# ICDI.net
KiCad netlist of a schematic drawn in Altium Designer
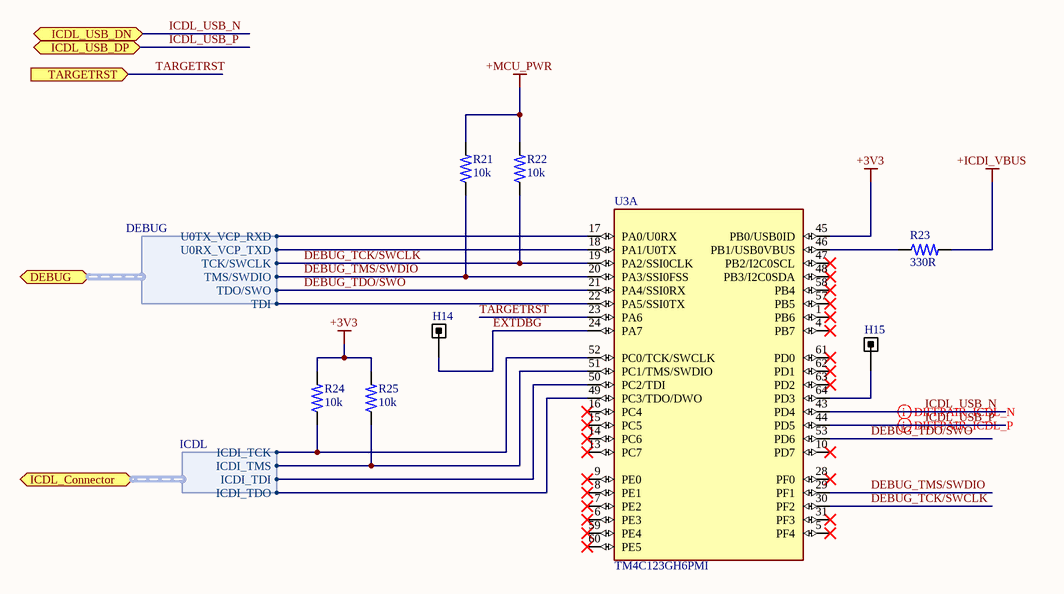
[diagram p0: ICDI.SchDoc]

(export (version "E")
  (design (tool "Eeschema 10.0.6"))
  (components
    (comp (ref "H14")
      (value "Test Point")
      (footprint "Test Point")
      (libsource (lib "Integrated_Library") (part "Test Point"))
    )
    (comp (ref "H15")
      (value "Test Point")
      (footprint "Test Point")
      (libsource (lib "Integrated_Library") (part "Test Point"))
    )
    (comp (ref "R21")
      (value "10k")
      (footprint "0402 RES")
      (fields
        (field (name "MANUFACTURER") "Yageo")
        (field (name "MANUFACTURER PART NUMBER") "RC0402FR-0710KL")
        (field (name "POWER") "62.5mW")
      )
      (libsource (lib "Integrated_Library") (part "0402 SMD Resistor"))
    )
    (comp (ref "R22")
      (value "10k")
      (footprint "0402 RES")
      (fields
        (field (name "MANUFACTURER") "Yageo")
        (field (name "MANUFACTURER PART NUMBER") "RC0402FR-0710KL")
        (field (name "POWER") "62.5mW")
      )
      (libsource (lib "Integrated_Library") (part "0402 SMD Resistor"))
    )
    (comp (ref "R23")
      (value "330R")
      (footprint "0402 RES")
      (fields
        (field (name "MANUFACTURER") "Vishay Dale")
        (field (name "MANUFACTURER PART NUMBER") "RCC0402330RFKED")
      )
      (libsource (lib "Integrated_Library") (part "0402 SMD Resistor"))
    )
    (comp (ref "R24")
      (value "10k")
      (footprint "0402 RES")
      (fields
        (field (name "MANUFACTURER") "Yageo")
        (field (name "MANUFACTURER PART NUMBER") "RC0402FR-0710KL")
        (field (name "POWER") "62.5mW")
      )
      (libsource (lib "Integrated_Library") (part "0402 SMD Resistor"))
    )
    (comp (ref "R25")
      (value "10k")
      (footprint "0402 RES")
      (fields
        (field (name "MANUFACTURER") "Yageo")
        (field (name "MANUFACTURER PART NUMBER") "RC0402FR-0710KL")
        (field (name "POWER") "62.5mW")
      )
      (libsource (lib "Integrated_Library") (part "0402 SMD Resistor"))
    )
    (comp (ref "U3")
      (value "TM4C123GH6PMI")
      (footprint "QFP50P1200X1200X160-64N")
      (fields (field (name "MF") "Texas Instruments"))
      (libsource (lib "Integrated_Library") (part "TM4C123GH6PMI"))
    )
  )
  (nets
    (net (code "3") (name "+3V3") (class "Default")
      (node (ref "R24") (pin "2") (pinfunction "2_2") (pintype "passive"))
      (node (ref "R25") (pin "2") (pinfunction "2_2") (pintype "passive"))
      (node (ref "U3") (pin "45") (pinfunction "PB0/USB0ID_45") (pintype "bidirectional"))
    )
    (net (code "4") (name "+ICDI_VBUS") (class "Default")
      (node (ref "R23") (pin "2") (pinfunction "2_2") (pintype "passive"))
    )
    (net (code "5") (name "+MCU_PWR") (class "Default")
      (node (ref "R21") (pin "2") (pinfunction "2_2") (pintype "passive"))
      (node (ref "R22") (pin "2") (pinfunction "2_2") (pintype "passive"))
    )
    (net (code "6") (name "/DEBUG_TCK{slash}SWCLK") (class "Default")
      (node (ref "R22") (pin "1") (pinfunction "1_1") (pintype "passive"))
      (node (ref "U3") (pin "19") (pinfunction "PA2/SSI0CLK_19") (pintype "bidirectional"))
      (node (ref "U3") (pin "30") (pinfunction "PF2_30") (pintype "bidirectional"))
    )
    (net (code "7") (name "/DEBUG_TDO{slash}SWO") (class "Default")
      (node (ref "U3") (pin "21") (pinfunction "PA4/SSI0RX_21") (pintype "bidirectional"))
      (node (ref "U3") (pin "53") (pinfunction "PD6_53") (pintype "bidirectional"))
    )
    (net (code "8") (name "/DEBUG_TMS{slash}SWDIO") (class "Default")
      (node (ref "R21") (pin "1") (pinfunction "1_1") (pintype "passive"))
      (node (ref "U3") (pin "20") (pinfunction "PA3/SSI0FSS_20") (pintype "bidirectional"))
      (node (ref "U3") (pin "29") (pinfunction "PF1_29") (pintype "bidirectional"))
    )
    (net (code "9") (name "/EXTDBG") (class "Default")
      (node (ref "H14") (pin "1") (pinfunction "1_1") (pintype "passive"))
      (node (ref "U3") (pin "24") (pinfunction "PA7_24") (pintype "bidirectional"))
    )
    (net (code "10") (name "/ICDI_TCK") (class "Default")
      (node (ref "R24") (pin "1") (pinfunction "1_1") (pintype "passive"))
      (node (ref "U3") (pin "52") (pinfunction "PC0/TCK/SWCLK_52") (pintype "bidirectional"))
    )
    (net (code "11") (name "/ICDI_TDI") (class "Default")
      (node (ref "U3") (pin "50") (pinfunction "PC2/TDI_50") (pintype "bidirectional"))
    )
    (net (code "12") (name "/ICDI_TDO") (class "Default")
      (node (ref "U3") (pin "49") (pinfunction "PC3/TDO/DWO_49") (pintype "bidirectional"))
    )
    (net (code "13") (name "/ICDI_TMS") (class "Default")
      (node (ref "R25") (pin "1") (pinfunction "1_1") (pintype "passive"))
      (node (ref "U3") (pin "51") (pinfunction "PC1/TMS/SWDIO_51") (pintype "bidirectional"))
    )
    (net (code "14") (name "/ICDL_USB_N") (class "Default")
      (node (ref "U3") (pin "43") (pinfunction "PD4_43") (pintype "bidirectional"))
    )
    (net (code "15") (name "/ICDL_USB_P") (class "Default")
      (node (ref "U3") (pin "44") (pinfunction "PD5_44") (pintype "bidirectional"))
    )
    (net (code "16") (name "/TARGETRST") (class "Default")
      (node (ref "U3") (pin "23") (pinfunction "PA6_23") (pintype "bidirectional"))
    )
    (net (code "17") (name "/TDI") (class "Default")
      (node (ref "U3") (pin "22") (pinfunction "PA5/SSI0TX_22") (pintype "bidirectional"))
    )
    (net (code "18") (name "/U0RX_VCP_TXD") (class "Default")
      (node (ref "U3") (pin "18") (pinfunction "PA1/U0TX_18") (pintype "bidirectional"))
    )
    (net (code "19") (name "/U0TX_VCP_RXD") (class "Default")
      (node (ref "U3") (pin "17") (pinfunction "PA0/U0RX_17") (pintype "bidirectional"))
    )
    (net (code "22") (name "Net-(U3A-PB1{slash}USB0VBUS)") (class "Default")
      (node (ref "R23") (pin "1") (pinfunction "1_1") (pintype "passive"))
      (node (ref "U3") (pin "46") (pinfunction "PB1/USB0VBUS_46") (pintype "bidirectional"))
    )
    (net (code "23") (name "Net-(U3A-PD3)") (class "Default")
      (node (ref "H15") (pin "1") (pinfunction "1_1") (pintype "passive"))
      (node (ref "U3") (pin "64") (pinfunction "PD3_64") (pintype "bidirectional"))
    )
    (net (code "24") (name "unconnected-(U3A-PB2{slash}I2C0SCL-Pad47)") (class "Default")
      (node (ref "U3") (pin "47") (pinfunction "PB2/I2C0SCL_47") (pintype "bidirectional+no_connect"))
    )
    (net (code "25") (name "unconnected-(U3A-PB3{slash}I2C0SDA-Pad48)") (class "Default")
      (node (ref "U3") (pin "48") (pinfunction "PB3/I2C0SDA_48") (pintype "bidirectional+no_connect"))
    )
    (net (code "26") (name "unconnected-(U3A-PB4-Pad58)") (class "Default")
      (node (ref "U3") (pin "58") (pinfunction "PB4_58") (pintype "bidirectional+no_connect"))
    )
    (net (code "27") (name "unconnected-(U3A-PB5-Pad57)") (class "Default")
      (node (ref "U3") (pin "57") (pinfunction "PB5_57") (pintype "bidirectional+no_connect"))
    )
    (net (code "28") (name "unconnected-(U3A-PB6-Pad1)") (class "Default")
      (node (ref "U3") (pin "1") (pinfunction "PB6_1") (pintype "bidirectional+no_connect"))
    )
    (net (code "29") (name "unconnected-(U3A-PB7-Pad4)") (class "Default")
      (node (ref "U3") (pin "4") (pinfunction "PB7_4") (pintype "bidirectional+no_connect"))
    )
    (net (code "30") (name "unconnected-(U3A-PC4-Pad16)") (class "Default")
      (node (ref "U3") (pin "16") (pinfunction "PC4_16") (pintype "bidirectional+no_connect"))
    )
    (net (code "31") (name "unconnected-(U3A-PC5-Pad15)") (class "Default")
      (node (ref "U3") (pin "15") (pinfunction "PC5_15") (pintype "bidirectional+no_connect"))
    )
    (net (code "32") (name "unconnected-(U3A-PC6-Pad14)") (class "Default")
      (node (ref "U3") (pin "14") (pinfunction "PC6_14") (pintype "bidirectional+no_connect"))
    )
    (net (code "33") (name "unconnected-(U3A-PC7-Pad13)") (class "Default")
      (node (ref "U3") (pin "13") (pinfunction "PC7_13") (pintype "bidirectional+no_connect"))
    )
    (net (code "34") (name "unconnected-(U3A-PD0-Pad61)") (class "Default")
      (node (ref "U3") (pin "61") (pinfunction "PD0_61") (pintype "bidirectional+no_connect"))
    )
    (net (code "35") (name "unconnected-(U3A-PD1-Pad62)") (class "Default")
      (node (ref "U3") (pin "62") (pinfunction "PD1_62") (pintype "bidirectional+no_connect"))
    )
    (net (code "36") (name "unconnected-(U3A-PD2-Pad63)") (class "Default")
      (node (ref "U3") (pin "63") (pinfunction "PD2_63") (pintype "bidirectional+no_connect"))
    )
    (net (code "37") (name "unconnected-(U3A-PD7-Pad10)") (class "Default")
      (node (ref "U3") (pin "10") (pinfunction "PD7_10") (pintype "bidirectional+no_connect"))
    )
    (net (code "38") (name "unconnected-(U3A-PE0-Pad9)") (class "Default")
      (node (ref "U3") (pin "9") (pinfunction "PE0_9") (pintype "bidirectional+no_connect"))
    )
    (net (code "39") (name "unconnected-(U3A-PE1-Pad8)") (class "Default")
      (node (ref "U3") (pin "8") (pinfunction "PE1_8") (pintype "bidirectional+no_connect"))
    )
    (net (code "40") (name "unconnected-(U3A-PE2-Pad7)") (class "Default")
      (node (ref "U3") (pin "7") (pinfunction "PE2_7") (pintype "bidirectional+no_connect"))
    )
    (net (code "41") (name "unconnected-(U3A-PE3-Pad6)") (class "Default")
      (node (ref "U3") (pin "6") (pinfunction "PE3_6") (pintype "bidirectional+no_connect"))
    )
    (net (code "42") (name "unconnected-(U3A-PE4-Pad59)") (class "Default")
      (node (ref "U3") (pin "59") (pinfunction "PE4_59") (pintype "bidirectional+no_connect"))
    )
    (net (code "43") (name "unconnected-(U3A-PE5-Pad60)") (class "Default")
      (node (ref "U3") (pin "60") (pinfunction "PE5_60") (pintype "bidirectional+no_connect"))
    )
    (net (code "44") (name "unconnected-(U3A-PF0-Pad28)") (class "Default")
      (node (ref "U3") (pin "28") (pinfunction "PF0_28") (pintype "bidirectional+no_connect"))
    )
    (net (code "45") (name "unconnected-(U3A-PF3-Pad31)") (class "Default")
      (node (ref "U3") (pin "31") (pinfunction "PF3_31") (pintype "bidirectional+no_connect"))
    )
    (net (code "46") (name "unconnected-(U3A-PF4-Pad5)") (class "Default")
      (node (ref "U3") (pin "5") (pinfunction "PF4_5") (pintype "bidirectional+no_connect"))
    )
  )
)
